# schematic.net
KiCad netlist of a schematic drawn in EasyEDA
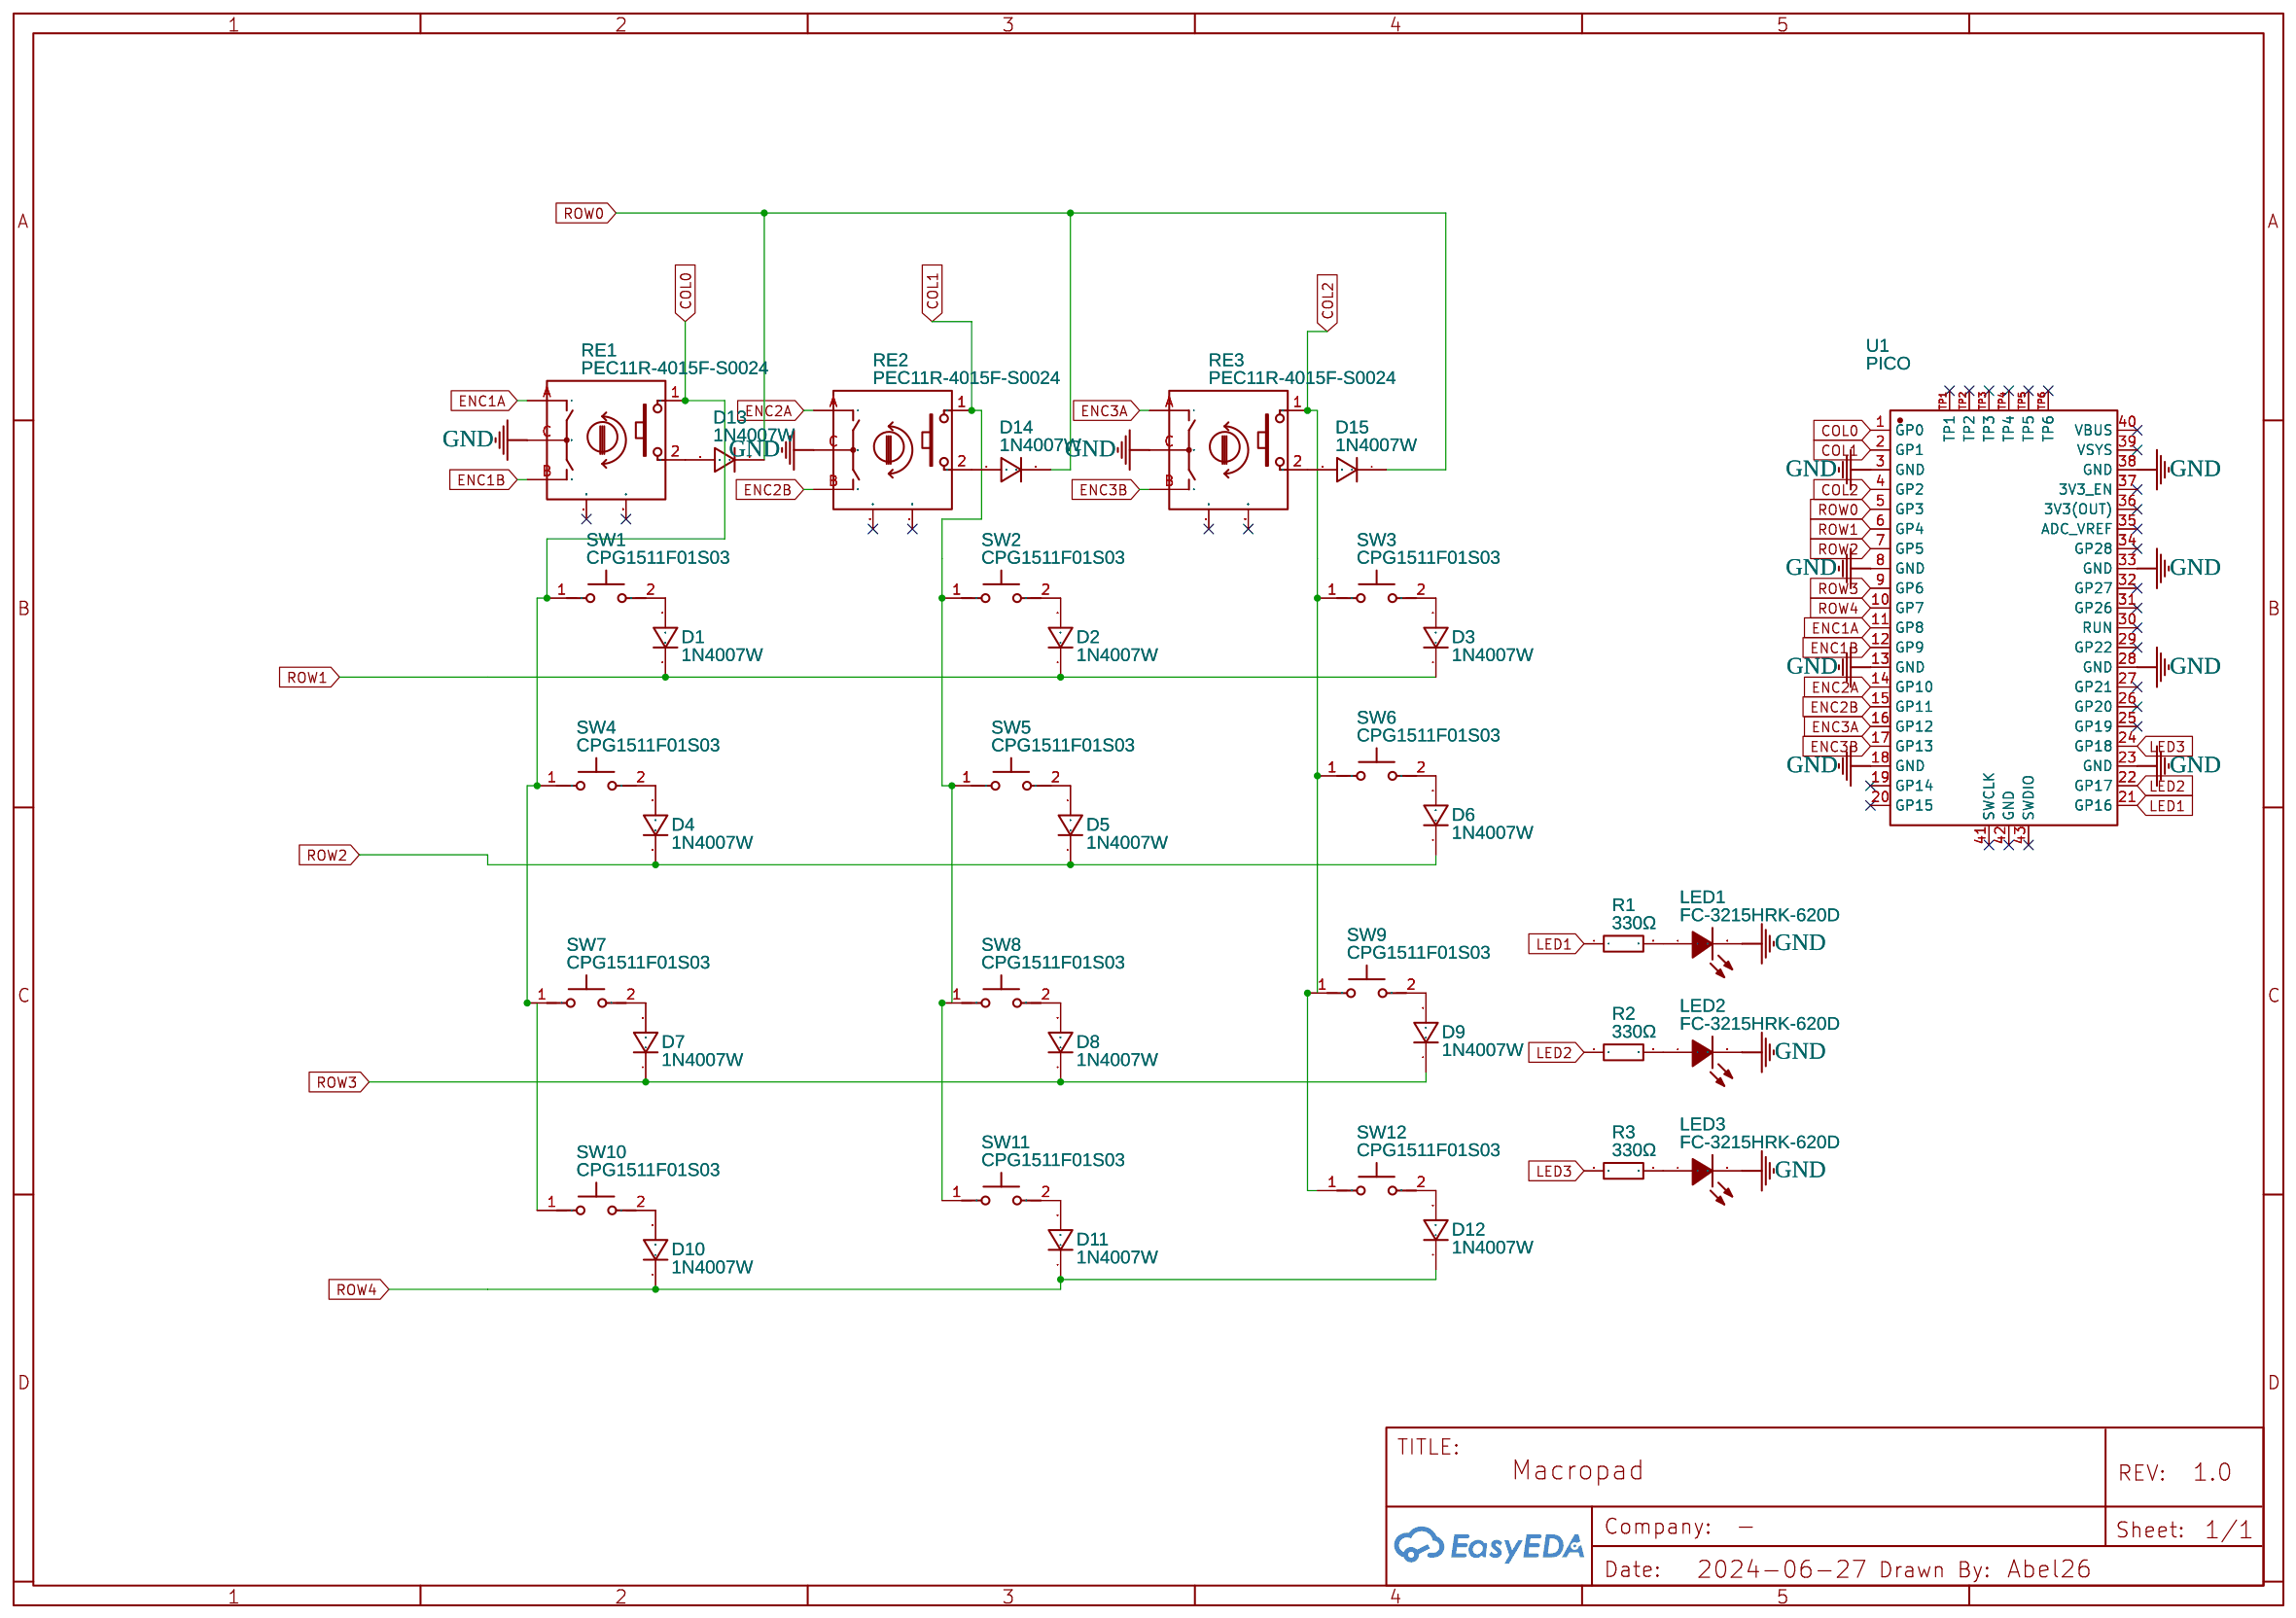
[diagram p0: schematic sheet]

(export (version "E")
  (design (tool "Eeschema 10.0.6"))
  (components
    (comp (ref "D1")
      (value "1N4007W")
      (fields (field (name "Manufacturer") "BLUE ROCKET"))
      (libsource (lib "") (part "1N4007W"))
    )
    (comp (ref "D2")
      (value "1N4007W")
      (fields (field (name "Manufacturer") "BLUE ROCKET"))
      (libsource (lib "") (part "1N4007W"))
    )
    (comp (ref "D3")
      (value "1N4007W")
      (fields (field (name "Manufacturer") "BLUE ROCKET"))
      (libsource (lib "") (part "1N4007W"))
    )
    (comp (ref "D4")
      (value "1N4007W")
      (fields (field (name "Manufacturer") "BLUE ROCKET"))
      (libsource (lib "") (part "1N4007W"))
    )
    (comp (ref "D5")
      (value "1N4007W")
      (fields (field (name "Manufacturer") "BLUE ROCKET"))
      (libsource (lib "") (part "1N4007W"))
    )
    (comp (ref "D6")
      (value "1N4007W")
      (fields (field (name "Manufacturer") "BLUE ROCKET"))
      (libsource (lib "") (part "1N4007W"))
    )
    (comp (ref "D7")
      (value "1N4007W")
      (fields (field (name "Manufacturer") "BLUE ROCKET"))
      (libsource (lib "") (part "1N4007W"))
    )
    (comp (ref "D8")
      (value "1N4007W")
      (fields (field (name "Manufacturer") "BLUE ROCKET"))
      (libsource (lib "") (part "1N4007W"))
    )
    (comp (ref "D9")
      (value "1N4007W")
      (fields (field (name "Manufacturer") "BLUE ROCKET"))
      (libsource (lib "") (part "1N4007W"))
    )
    (comp (ref "D10")
      (value "1N4007W")
      (fields (field (name "Manufacturer") "BLUE ROCKET"))
      (libsource (lib "") (part "1N4007W"))
    )
    (comp (ref "D11")
      (value "1N4007W")
      (fields (field (name "Manufacturer") "BLUE ROCKET"))
      (libsource (lib "") (part "1N4007W"))
    )
    (comp (ref "D12")
      (value "1N4007W")
      (fields (field (name "Manufacturer") "BLUE ROCKET"))
      (libsource (lib "") (part "1N4007W"))
    )
    (comp (ref "D13")
      (value "1N4007W")
      (fields (field (name "Manufacturer") "BLUE ROCKET"))
      (libsource (lib "") (part "1N4007W_1"))
    )
    (comp (ref "D14")
      (value "1N4007W")
      (fields (field (name "Manufacturer") "BLUE ROCKET"))
      (libsource (lib "") (part "1N4007W_1"))
    )
    (comp (ref "D15")
      (value "1N4007W")
      (fields (field (name "Manufacturer") "BLUE ROCKET"))
      (libsource (lib "") (part "1N4007W_1"))
    )
    (comp (ref "LED1")
      (value "FC-3215HRK-620D")
      (fields (field (name "Manufacturer Part") "NCD1206R1") (field (name "Manufacturer") "国星光电"))
      (libsource (lib "") (part "FC-3215HRK-620D"))
    )
    (comp (ref "LED2")
      (value "FC-3215HRK-620D")
      (fields (field (name "Manufacturer Part") "NCD1206R1") (field (name "Manufacturer") "国星光电"))
      (libsource (lib "") (part "FC-3215HRK-620D"))
    )
    (comp (ref "LED3")
      (value "FC-3215HRK-620D")
      (fields (field (name "Manufacturer Part") "NCD1206R1") (field (name "Manufacturer") "国星光电"))
      (libsource (lib "") (part "FC-3215HRK-620D"))
    )
    (comp (ref "R1")
      (value "330Ω")
      (fields
        (field (name "Manufacturer Part") "0805W8J0331T5E")
        (field (name "Manufacturer") "UNI-ROYAL(厚声)")
      )
      (libsource (lib "") (part "0805W8J0331T5E"))
    )
    (comp (ref "R2")
      (value "330Ω")
      (fields
        (field (name "Manufacturer Part") "0805W8J0331T5E")
        (field (name "Manufacturer") "UNI-ROYAL(厚声)")
      )
      (libsource (lib "") (part "0805W8J0331T5E"))
    )
    (comp (ref "R3")
      (value "330Ω")
      (fields
        (field (name "Manufacturer Part") "0805W8J0331T5E")
        (field (name "Manufacturer") "UNI-ROYAL(厚声)")
      )
      (libsource (lib "") (part "0805W8J0331T5E"))
    )
    (comp (ref "RE1")
      (value "PEC11R-4015F-S0024")
      (fields (field (name "Manufacturer") "BOURNS"))
      (libsource (lib "") (part "PEC11R-4015F-S0024"))
    )
    (comp (ref "RE2")
      (value "PEC11R-4015F-S0024")
      (fields (field (name "Manufacturer") "BOURNS"))
      (libsource (lib "") (part "PEC11R-4015F-S0024"))
    )
    (comp (ref "RE3")
      (value "PEC11R-4015F-S0024")
      (fields (field (name "Manufacturer") "BOURNS"))
      (libsource (lib "") (part "PEC11R-4015F-S0024"))
    )
    (comp (ref "SW1")
      (value "CPG1511F01S03")
      (fields (field (name "Manufacturer") "Kailh(凯华)"))
      (libsource (lib "") (part "CPG1511F01S03"))
    )
    (comp (ref "SW2")
      (value "CPG1511F01S03")
      (fields (field (name "Manufacturer") "Kailh(凯华)"))
      (libsource (lib "") (part "CPG1511F01S03"))
    )
    (comp (ref "SW3")
      (value "CPG1511F01S03")
      (fields (field (name "Manufacturer") "Kailh(凯华)"))
      (libsource (lib "") (part "CPG1511F01S03"))
    )
    (comp (ref "SW4")
      (value "CPG1511F01S03")
      (fields (field (name "Manufacturer") "Kailh(凯华)"))
      (libsource (lib "") (part "CPG1511F01S03"))
    )
    (comp (ref "SW5")
      (value "CPG1511F01S03")
      (fields (field (name "Manufacturer") "Kailh(凯华)"))
      (libsource (lib "") (part "CPG1511F01S03"))
    )
    (comp (ref "SW6")
      (value "CPG1511F01S03")
      (fields (field (name "Manufacturer") "Kailh(凯华)"))
      (libsource (lib "") (part "CPG1511F01S03"))
    )
    (comp (ref "SW7")
      (value "CPG1511F01S03")
      (fields (field (name "Manufacturer") "Kailh(凯华)"))
      (libsource (lib "") (part "CPG1511F01S03"))
    )
    (comp (ref "SW8")
      (value "CPG1511F01S03")
      (fields (field (name "Manufacturer") "Kailh(凯华)"))
      (libsource (lib "") (part "CPG1511F01S03"))
    )
    (comp (ref "SW9")
      (value "CPG1511F01S03")
      (fields (field (name "Manufacturer") "Kailh(凯华)"))
      (libsource (lib "") (part "CPG1511F01S03"))
    )
    (comp (ref "SW10")
      (value "CPG1511F01S03")
      (fields (field (name "Manufacturer") "Kailh(凯华)"))
      (libsource (lib "") (part "CPG1511F01S03"))
    )
    (comp (ref "SW11")
      (value "CPG1511F01S03")
      (fields (field (name "Manufacturer") "Kailh(凯华)"))
      (libsource (lib "") (part "CPG1511F01S03"))
    )
    (comp (ref "SW12")
      (value "CPG1511F01S03")
      (fields (field (name "Manufacturer") "Kailh(凯华)"))
      (libsource (lib "") (part "CPG1511F01S03"))
    )
    (comp (ref "U1")
      (value "PICO")
      (fields (field (name "Manufacturer") "Raspberry Pi(树莓派)"))
      (libsource (lib "") (part "PICO"))
    )
  )
  (nets
    (net (code "1") (name "COL0") (class "Default")
      (node (ref "RE1") (pin "1") (pinfunction "1_1") (pintype "unspecified"))
      (node (ref "SW1") (pin "1") (pinfunction "1_1") (pintype "unspecified"))
      (node (ref "SW10") (pin "1") (pinfunction "1_1") (pintype "unspecified"))
      (node (ref "SW4") (pin "1") (pinfunction "1_1") (pintype "unspecified"))
      (node (ref "SW7") (pin "1") (pinfunction "1_1") (pintype "unspecified"))
      (node (ref "U1") (pin "1") (pinfunction "GP0_1") (pintype "unspecified"))
    )
    (net (code "2") (name "COL1") (class "Default")
      (node (ref "RE2") (pin "1") (pinfunction "1_1") (pintype "unspecified"))
      (node (ref "SW11") (pin "1") (pinfunction "1_1") (pintype "unspecified"))
      (node (ref "SW2") (pin "1") (pinfunction "1_1") (pintype "unspecified"))
      (node (ref "SW5") (pin "1") (pinfunction "1_1") (pintype "unspecified"))
      (node (ref "SW8") (pin "1") (pinfunction "1_1") (pintype "unspecified"))
      (node (ref "U1") (pin "2") (pinfunction "GP1_2") (pintype "unspecified"))
    )
    (net (code "3") (name "COL2") (class "Default")
      (node (ref "RE3") (pin "1") (pinfunction "1_1") (pintype "unspecified"))
      (node (ref "SW12") (pin "1") (pinfunction "1_1") (pintype "unspecified"))
      (node (ref "SW3") (pin "1") (pinfunction "1_1") (pintype "unspecified"))
      (node (ref "SW6") (pin "1") (pinfunction "1_1") (pintype "unspecified"))
      (node (ref "SW9") (pin "1") (pinfunction "1_1") (pintype "unspecified"))
      (node (ref "U1") (pin "4") (pinfunction "GP2_4") (pintype "unspecified"))
    )
    (net (code "4") (name "ENC1A") (class "Default")
      (node (ref "RE1") (pin "A") (pinfunction "A_A") (pintype "unspecified"))
      (node (ref "U1") (pin "11") (pinfunction "GP8_11") (pintype "unspecified"))
    )
    (net (code "5") (name "ENC1B") (class "Default")
      (node (ref "RE1") (pin "B") (pinfunction "B_B") (pintype "unspecified"))
      (node (ref "U1") (pin "12") (pinfunction "GP9_12") (pintype "unspecified"))
    )
    (net (code "6") (name "ENC2A") (class "Default")
      (node (ref "RE2") (pin "A") (pinfunction "A_A") (pintype "unspecified"))
      (node (ref "U1") (pin "14") (pinfunction "GP10_14") (pintype "unspecified"))
    )
    (net (code "7") (name "ENC2B") (class "Default")
      (node (ref "RE2") (pin "B") (pinfunction "B_B") (pintype "unspecified"))
      (node (ref "U1") (pin "15") (pinfunction "GP11_15") (pintype "unspecified"))
    )
    (net (code "8") (name "ENC3A") (class "Default")
      (node (ref "RE3") (pin "A") (pinfunction "A_A") (pintype "unspecified"))
      (node (ref "U1") (pin "16") (pinfunction "GP12_16") (pintype "unspecified"))
    )
    (net (code "9") (name "ENC3B") (class "Default")
      (node (ref "RE3") (pin "B") (pinfunction "B_B") (pintype "unspecified"))
      (node (ref "U1") (pin "17") (pinfunction "GP13_17") (pintype "unspecified"))
    )
    (net (code "10") (name "GND") (class "Default")
      (node (ref "LED1") (pin "2") (pinfunction "K_2") (pintype "unspecified"))
      (node (ref "LED2") (pin "2") (pinfunction "K_2") (pintype "unspecified"))
      (node (ref "LED3") (pin "2") (pinfunction "K_2") (pintype "unspecified"))
      (node (ref "RE1") (pin "C") (pinfunction "C_C") (pintype "unspecified"))
      (node (ref "RE2") (pin "C") (pinfunction "C_C") (pintype "unspecified"))
      (node (ref "RE3") (pin "C") (pinfunction "C_C") (pintype "unspecified"))
      (node (ref "U1") (pin "13") (pinfunction "GND_13") (pintype "unspecified"))
      (node (ref "U1") (pin "18") (pinfunction "GND_18") (pintype "unspecified"))
      (node (ref "U1") (pin "23") (pinfunction "GND_23") (pintype "unspecified"))
      (node (ref "U1") (pin "28") (pinfunction "GND_28") (pintype "unspecified"))
      (node (ref "U1") (pin "3") (pinfunction "GND_3") (pintype "unspecified"))
      (node (ref "U1") (pin "33") (pinfunction "GND_33") (pintype "unspecified"))
      (node (ref "U1") (pin "38") (pinfunction "GND_38") (pintype "unspecified"))
      (node (ref "U1") (pin "8") (pinfunction "GND_8") (pintype "unspecified"))
    )
    (net (code "11") (name "LED1") (class "Default")
      (node (ref "R1") (pin "1") (pinfunction "1_1") (pintype "input"))
      (node (ref "U1") (pin "21") (pinfunction "GP16_21") (pintype "unspecified"))
    )
    (net (code "12") (name "LED2") (class "Default")
      (node (ref "R2") (pin "1") (pinfunction "1_1") (pintype "input"))
      (node (ref "U1") (pin "22") (pinfunction "GP17_22") (pintype "unspecified"))
    )
    (net (code "13") (name "LED3") (class "Default")
      (node (ref "R3") (pin "1") (pinfunction "1_1") (pintype "input"))
      (node (ref "U1") (pin "24") (pinfunction "GP18_24") (pintype "unspecified"))
    )
    (net (code "14") (name "Net-(D1-Pad2)") (class "Default")
      (node (ref "D1") (pin "2") (pinfunction "2_2") (pintype "unspecified"))
      (node (ref "SW1") (pin "2") (pinfunction "2_2") (pintype "unspecified"))
    )
    (net (code "15") (name "Net-(D2-Pad2)") (class "Default")
      (node (ref "D2") (pin "2") (pinfunction "2_2") (pintype "unspecified"))
      (node (ref "SW2") (pin "2") (pinfunction "2_2") (pintype "unspecified"))
    )
    (net (code "16") (name "Net-(D3-Pad2)") (class "Default")
      (node (ref "D3") (pin "2") (pinfunction "2_2") (pintype "unspecified"))
      (node (ref "SW3") (pin "2") (pinfunction "2_2") (pintype "unspecified"))
    )
    (net (code "17") (name "Net-(D4-Pad2)") (class "Default")
      (node (ref "D4") (pin "2") (pinfunction "2_2") (pintype "unspecified"))
      (node (ref "SW4") (pin "2") (pinfunction "2_2") (pintype "unspecified"))
    )
    (net (code "18") (name "Net-(D5-Pad2)") (class "Default")
      (node (ref "D5") (pin "2") (pinfunction "2_2") (pintype "unspecified"))
      (node (ref "SW5") (pin "2") (pinfunction "2_2") (pintype "unspecified"))
    )
    (net (code "19") (name "Net-(D6-Pad2)") (class "Default")
      (node (ref "D6") (pin "2") (pinfunction "2_2") (pintype "unspecified"))
      (node (ref "SW6") (pin "2") (pinfunction "2_2") (pintype "unspecified"))
    )
    (net (code "20") (name "Net-(D7-Pad2)") (class "Default")
      (node (ref "D7") (pin "2") (pinfunction "2_2") (pintype "unspecified"))
      (node (ref "SW7") (pin "2") (pinfunction "2_2") (pintype "unspecified"))
    )
    (net (code "21") (name "Net-(D8-Pad2)") (class "Default")
      (node (ref "D8") (pin "2") (pinfunction "2_2") (pintype "unspecified"))
      (node (ref "SW8") (pin "2") (pinfunction "2_2") (pintype "unspecified"))
    )
    (net (code "22") (name "Net-(D9-Pad2)") (class "Default")
      (node (ref "D9") (pin "2") (pinfunction "2_2") (pintype "unspecified"))
      (node (ref "SW9") (pin "2") (pinfunction "2_2") (pintype "unspecified"))
    )
    (net (code "23") (name "Net-(D10-Pad2)") (class "Default")
      (node (ref "D10") (pin "2") (pinfunction "2_2") (pintype "unspecified"))
      (node (ref "SW10") (pin "2") (pinfunction "2_2") (pintype "unspecified"))
    )
    (net (code "24") (name "Net-(D11-Pad2)") (class "Default")
      (node (ref "D11") (pin "2") (pinfunction "2_2") (pintype "unspecified"))
      (node (ref "SW11") (pin "2") (pinfunction "2_2") (pintype "unspecified"))
    )
    (net (code "25") (name "Net-(D12-Pad2)") (class "Default")
      (node (ref "D12") (pin "2") (pinfunction "2_2") (pintype "unspecified"))
      (node (ref "SW12") (pin "2") (pinfunction "2_2") (pintype "unspecified"))
    )
    (net (code "26") (name "Net-(D13-Pad2)") (class "Default")
      (node (ref "D13") (pin "2") (pinfunction "2_2") (pintype "unspecified"))
      (node (ref "RE1") (pin "2") (pinfunction "2_2") (pintype "unspecified"))
    )
    (net (code "27") (name "Net-(D14-Pad2)") (class "Default")
      (node (ref "D14") (pin "2") (pinfunction "2_2") (pintype "unspecified"))
      (node (ref "RE2") (pin "2") (pinfunction "2_2") (pintype "unspecified"))
    )
    (net (code "28") (name "Net-(D15-Pad2)") (class "Default")
      (node (ref "D15") (pin "2") (pinfunction "2_2") (pintype "unspecified"))
      (node (ref "RE3") (pin "2") (pinfunction "2_2") (pintype "unspecified"))
    )
    (net (code "29") (name "Net-(LED1-A)") (class "Default")
      (node (ref "LED1") (pin "1") (pinfunction "A_1") (pintype "unspecified"))
      (node (ref "R1") (pin "2") (pinfunction "2_2") (pintype "input"))
    )
    (net (code "30") (name "Net-(LED2-A)") (class "Default")
      (node (ref "LED2") (pin "1") (pinfunction "A_1") (pintype "unspecified"))
      (node (ref "R2") (pin "2") (pinfunction "2_2") (pintype "input"))
    )
    (net (code "31") (name "Net-(LED3-A)") (class "Default")
      (node (ref "LED3") (pin "1") (pinfunction "A_1") (pintype "unspecified"))
      (node (ref "R3") (pin "2") (pinfunction "2_2") (pintype "input"))
    )
    (net (code "32") (name "ROW0") (class "Default")
      (node (ref "D13") (pin "1") (pinfunction "1_1") (pintype "unspecified"))
      (node (ref "D14") (pin "1") (pinfunction "1_1") (pintype "unspecified"))
      (node (ref "D15") (pin "1") (pinfunction "1_1") (pintype "unspecified"))
      (node (ref "U1") (pin "5") (pinfunction "GP3_5") (pintype "unspecified"))
    )
    (net (code "33") (name "ROW1") (class "Default")
      (node (ref "D1") (pin "1") (pinfunction "1_1") (pintype "unspecified"))
      (node (ref "D2") (pin "1") (pinfunction "1_1") (pintype "unspecified"))
      (node (ref "D3") (pin "1") (pinfunction "1_1") (pintype "unspecified"))
      (node (ref "U1") (pin "6") (pinfunction "GP4_6") (pintype "unspecified"))
    )
    (net (code "34") (name "ROW2") (class "Default")
      (node (ref "D4") (pin "1") (pinfunction "1_1") (pintype "unspecified"))
      (node (ref "D5") (pin "1") (pinfunction "1_1") (pintype "unspecified"))
      (node (ref "D6") (pin "1") (pinfunction "1_1") (pintype "unspecified"))
      (node (ref "U1") (pin "7") (pinfunction "GP5_7") (pintype "unspecified"))
    )
    (net (code "35") (name "ROW3") (class "Default")
      (node (ref "D7") (pin "1") (pinfunction "1_1") (pintype "unspecified"))
      (node (ref "D8") (pin "1") (pinfunction "1_1") (pintype "unspecified"))
      (node (ref "D9") (pin "1") (pinfunction "1_1") (pintype "unspecified"))
      (node (ref "U1") (pin "9") (pinfunction "GP6_9") (pintype "unspecified"))
    )
    (net (code "36") (name "ROW4") (class "Default")
      (node (ref "D10") (pin "1") (pinfunction "1_1") (pintype "unspecified"))
      (node (ref "D11") (pin "1") (pinfunction "1_1") (pintype "unspecified"))
      (node (ref "D12") (pin "1") (pinfunction "1_1") (pintype "unspecified"))
      (node (ref "U1") (pin "10") (pinfunction "GP7_10") (pintype "unspecified"))
    )
    (net (code "37") (name "unconnected-(RE1-PadMT1)") (class "Default")
      (node (ref "RE1") (pin "MT1") (pinfunction "MT1_MT1") (pintype "unspecified+no_connect"))
    )
    (net (code "38") (name "unconnected-(RE1-PadMT2)") (class "Default")
      (node (ref "RE1") (pin "MT2") (pinfunction "MT2_MT2") (pintype "unspecified+no_connect"))
    )
    (net (code "39") (name "unconnected-(RE2-PadMT1)") (class "Default")
      (node (ref "RE2") (pin "MT1") (pinfunction "MT1_MT1") (pintype "unspecified+no_connect"))
    )
    (net (code "40") (name "unconnected-(RE2-PadMT2)") (class "Default")
      (node (ref "RE2") (pin "MT2") (pinfunction "MT2_MT2") (pintype "unspecified+no_connect"))
    )
    (net (code "41") (name "unconnected-(RE3-PadMT1)") (class "Default")
      (node (ref "RE3") (pin "MT1") (pinfunction "MT1_MT1") (pintype "unspecified+no_connect"))
    )
    (net (code "42") (name "unconnected-(RE3-PadMT2)") (class "Default")
      (node (ref "RE3") (pin "MT2") (pinfunction "MT2_MT2") (pintype "unspecified+no_connect"))
    )
    (net (code "43") (name "unconnected-(U1-3V3(OUT)-Pad36)") (class "Default")
      (node (ref "U1") (pin "36") (pinfunction "3V3(OUT)_36") (pintype "unspecified+no_connect"))
    )
    (net (code "44") (name "unconnected-(U1-3V3_EN-Pad37)") (class "Default")
      (node (ref "U1") (pin "37") (pinfunction "3V3_EN_37") (pintype "unspecified+no_connect"))
    )
    (net (code "45") (name "unconnected-(U1-ADC_VREF-Pad35)") (class "Default")
      (node (ref "U1") (pin "35") (pinfunction "ADC_VREF_35") (pintype "unspecified+no_connect"))
    )
    (net (code "46") (name "unconnected-(U1-GND-Pad42)") (class "Default")
      (node (ref "U1") (pin "42") (pinfunction "GND_42") (pintype "unspecified+no_connect"))
    )
    (net (code "47") (name "unconnected-(U1-GP14-Pad19)") (class "Default")
      (node (ref "U1") (pin "19") (pinfunction "GP14_19") (pintype "unspecified+no_connect"))
    )
    (net (code "48") (name "unconnected-(U1-GP15-Pad20)") (class "Default")
      (node (ref "U1") (pin "20") (pinfunction "GP15_20") (pintype "unspecified+no_connect"))
    )
    (net (code "49") (name "unconnected-(U1-GP19-Pad25)") (class "Default")
      (node (ref "U1") (pin "25") (pinfunction "GP19_25") (pintype "unspecified+no_connect"))
    )
    (net (code "50") (name "unconnected-(U1-GP20-Pad26)") (class "Default")
      (node (ref "U1") (pin "26") (pinfunction "GP20_26") (pintype "unspecified+no_connect"))
    )
    (net (code "51") (name "unconnected-(U1-GP21-Pad27)") (class "Default")
      (node (ref "U1") (pin "27") (pinfunction "GP21_27") (pintype "unspecified+no_connect"))
    )
    (net (code "52") (name "unconnected-(U1-GP22-Pad29)") (class "Default")
      (node (ref "U1") (pin "29") (pinfunction "GP22_29") (pintype "unspecified+no_connect"))
    )
    (net (code "53") (name "unconnected-(U1-GP26-Pad31)") (class "Default")
      (node (ref "U1") (pin "31") (pinfunction "GP26_31") (pintype "unspecified+no_connect"))
    )
    (net (code "54") (name "unconnected-(U1-GP27-Pad32)") (class "Default")
      (node (ref "U1") (pin "32") (pinfunction "GP27_32") (pintype "unspecified+no_connect"))
    )
    (net (code "55") (name "unconnected-(U1-GP28-Pad34)") (class "Default")
      (node (ref "U1") (pin "34") (pinfunction "GP28_34") (pintype "unspecified+no_connect"))
    )
    (net (code "56") (name "unconnected-(U1-PadTP1)") (class "Default")
      (node (ref "U1") (pin "TP1") (pinfunction "TP1_TP1") (pintype "unspecified+no_connect"))
    )
    (net (code "57") (name "unconnected-(U1-PadTP2)") (class "Default")
      (node (ref "U1") (pin "TP2") (pinfunction "TP2_TP2") (pintype "unspecified+no_connect"))
    )
    (net (code "58") (name "unconnected-(U1-PadTP3)") (class "Default")
      (node (ref "U1") (pin "TP3") (pinfunction "TP3_TP3") (pintype "unspecified+no_connect"))
    )
    (net (code "59") (name "unconnected-(U1-PadTP4)") (class "Default")
      (node (ref "U1") (pin "TP4") (pinfunction "TP4_TP4") (pintype "unspecified+no_connect"))
    )
    (net (code "60") (name "unconnected-(U1-PadTP5)") (class "Default")
      (node (ref "U1") (pin "TP5") (pinfunction "TP5_TP5") (pintype "unspecified+no_connect"))
    )
    (net (code "61") (name "unconnected-(U1-PadTP6)") (class "Default")
      (node (ref "U1") (pin "TP6") (pinfunction "TP6_TP6") (pintype "unspecified+no_connect"))
    )
    (net (code "62") (name "unconnected-(U1-RUN-Pad30)") (class "Default")
      (node (ref "U1") (pin "30") (pinfunction "RUN_30") (pintype "unspecified+no_connect"))
    )
    (net (code "63") (name "unconnected-(U1-SWCLK-Pad41)") (class "Default")
      (node (ref "U1") (pin "41") (pinfunction "SWCLK_41") (pintype "unspecified+no_connect"))
    )
    (net (code "64") (name "unconnected-(U1-SWDIO-Pad43)") (class "Default")
      (node (ref "U1") (pin "43") (pinfunction "SWDIO_43") (pintype "unspecified+no_connect"))
    )
    (net (code "65") (name "unconnected-(U1-VBUS-Pad40)") (class "Default")
      (node (ref "U1") (pin "40") (pinfunction "VBUS_40") (pintype "unspecified+no_connect"))
    )
    (net (code "66") (name "unconnected-(U1-VSYS-Pad39)") (class "Default")
      (node (ref "U1") (pin "39") (pinfunction "VSYS_39") (pintype "unspecified+no_connect"))
    )
  )
)
